# tetris_bigger_mega.net
KiCad netlist of a schematic drawn in EAGLE
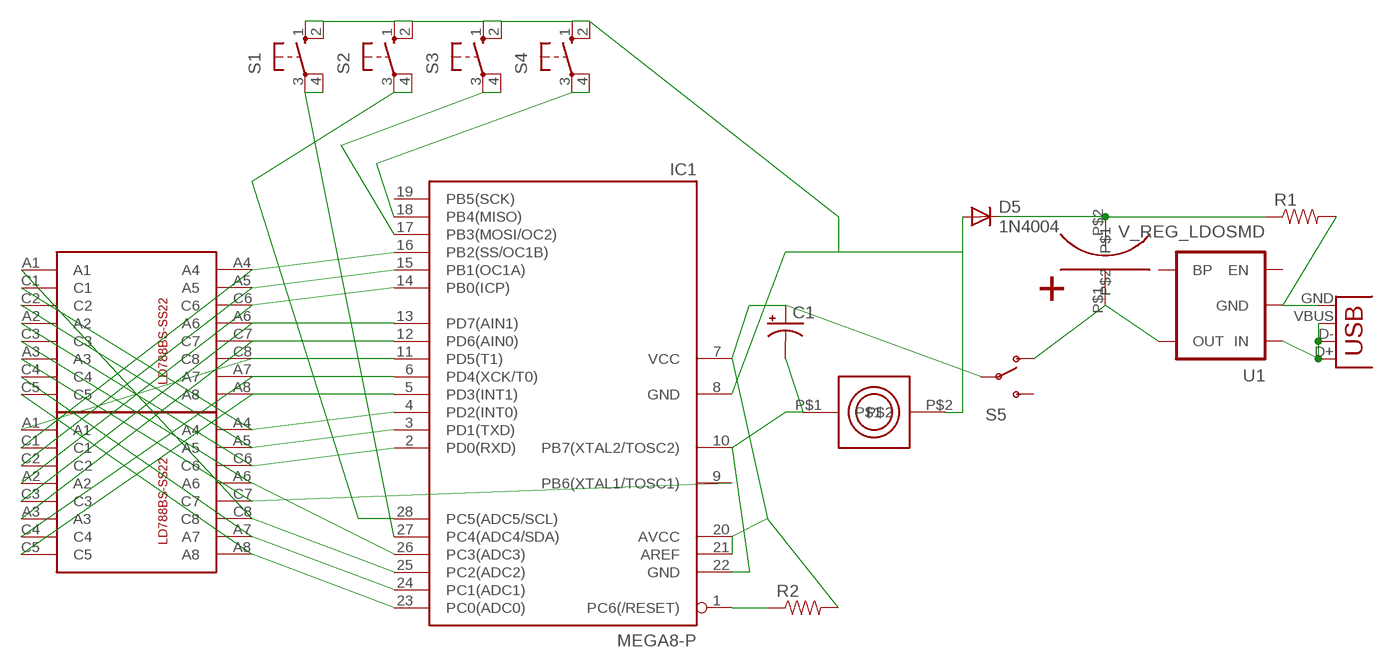
[diagram p0: schematic, sheet 1]

(export (version "E")
  (design (tool "Eeschema 10.0.6"))
  (components
    (comp (ref "C1")
      (value "CAP_POLPTH1")
      (footprint "eagle-import:CPOL-RADIAL-100UF-25V")
      (libsource (lib "eagle-import") (part "CAP_POLPTH1"))
    )
    (comp (ref "D5")
      (value "1N4004")
      (footprint "eagle-import:DO41-10")
      (libsource (lib "eagle-import") (part "1N4004"))
    )
    (comp (ref "IC1")
      (value "MEGA8-P")
      (footprint "eagle-import:DIL28-3")
      (libsource (lib "eagle-import") (part "MEGA8-P"))
    )
    (comp (ref "R1")
      (value "RESISTORPTH1")
      (footprint "eagle-import:AXIAL-0.3")
      (libsource (lib "eagle-import") (part "RESISTORPTH1"))
    )
    (comp (ref "R2")
      (value "RESISTORPTH1")
      (footprint "eagle-import:AXIAL-0.3")
      (libsource (lib "eagle-import") (part "RESISTORPTH1"))
    )
    (comp (ref "S1")
      (value "10-XX")
      (footprint "eagle-import:B3F-10XX")
      (fields (field (name "MPN") "B3F-1000"))
      (libsource (lib "eagle-import") (part "10-XX"))
    )
    (comp (ref "S2")
      (value "10-XX")
      (footprint "eagle-import:B3F-10XX")
      (fields (field (name "MPN") "B3F-1000"))
      (libsource (lib "eagle-import") (part "10-XX"))
    )
    (comp (ref "S3")
      (value "10-XX")
      (footprint "eagle-import:B3F-10XX")
      (fields (field (name "MPN") "B3F-1000"))
      (libsource (lib "eagle-import") (part "10-XX"))
    )
    (comp (ref "S4")
      (value "10-XX")
      (footprint "eagle-import:B3F-10XX")
      (fields (field (name "MPN") "B3F-1000"))
      (libsource (lib "eagle-import") (part "10-XX"))
    )
    (comp (ref "S5")
      (value "SWITCH-SPSTSMD2")
      (footprint "eagle-import:SWITCH-SPDT-SMD")
      (libsource (lib "eagle-import") (part "SWITCH-SPSTSMD2"))
    )
    (comp (ref "U$1")
      (value "LD-1088BS")
      (footprint "eagle-import:LD-1088BS")
      (libsource (lib "eagle-import") (part "LD-1088BS"))
    )
    (comp (ref "U$2")
      (value "LD-1088BS")
      (footprint "eagle-import:LD-1088BS")
      (libsource (lib "eagle-import") (part "LD-1088BS"))
    )
    (comp (ref "U$4")
      (value "I-80450RF")
      (footprint "eagle-import:ISK4.1K_I-80450RF_I2G")
      (libsource (lib "eagle-import") (part "I-80450RF"))
    )
    (comp (ref "U$5")
      (value "NICHICON_12F")
      (footprint "eagle-import:NICHICON_10X30")
      (libsource (lib "eagle-import") (part "NICHICON_12F"))
    )
    (comp (ref "U1")
      (value "V_REG_LDOSMD")
      (footprint "eagle-import:SOT23-5")
      (libsource (lib "eagle-import") (part "V_REG_LDOSMD"))
    )
    (comp (ref "X1")
      (value "USB-MICROB")
      (footprint "eagle-import:USB-MICROB")
      (libsource (lib "eagle-import") (part "USB-MICROB"))
    )
  )
  (nets
    (net (code "1") (name "Net-(C1-+)") (class "Default")
      (node (ref "C1") (pin "1") (pinfunction "+_1") (pintype "passive"))
      (node (ref "IC1") (pin "20") (pinfunction "AVCC_20") (pintype "power_in"))
      (node (ref "IC1") (pin "21") (pinfunction "AREF_21") (pintype "passive"))
      (node (ref "IC1") (pin "7") (pinfunction "VCC_7") (pintype "power_in"))
      (node (ref "R2") (pin "P$2") (pinfunction "2_P$2") (pintype "passive"))
      (node (ref "S5") (pin "2") (pinfunction "P_2") (pintype "passive"))
    )
    (net (code "2") (name "Net-(C1--)") (class "Default")
      (node (ref "C1") (pin "2") (pinfunction "-_2") (pintype "passive"))
      (node (ref "IC1") (pin "10") (pinfunction "PB7(XTAL2/TOSC2)_10") (pintype "bidirectional"))
      (node (ref "IC1") (pin "22") (pinfunction "GND_22") (pintype "power_in"))
      (node (ref "U$4") (pin "P$1") (pinfunction "P$1_P$1") (pintype "bidirectional"))
    )
    (net (code "3") (name "Net-(IC1-PB0(ICP))") (class "Default")
      (node (ref "IC1") (pin "14") (pinfunction "PB0(ICP)_14") (pintype "bidirectional"))
      (node (ref "U$1") (pin "A2") (pinfunction "A2_A2") (pintype "bidirectional"))
      (node (ref "U$2") (pin "C6") (pinfunction "C6_C6") (pintype "bidirectional"))
    )
    (net (code "4") (name "Net-(IC1-PB1(OC1A))") (class "Default")
      (node (ref "IC1") (pin "15") (pinfunction "PB1(OC1A)_15") (pintype "bidirectional"))
      (node (ref "U$1") (pin "C2") (pinfunction "C2_C2") (pintype "bidirectional"))
      (node (ref "U$2") (pin "A5") (pinfunction "A5_A5") (pintype "bidirectional"))
    )
    (net (code "5") (name "Net-(IC1-PB2(SS{slash}OC1B))") (class "Default")
      (node (ref "IC1") (pin "16") (pinfunction "PB2(SS/OC1B)_16") (pintype "bidirectional"))
      (node (ref "U$1") (pin "C1") (pinfunction "C1_C1") (pintype "bidirectional"))
      (node (ref "U$2") (pin "A4") (pinfunction "A4_A4") (pintype "bidirectional"))
    )
    (net (code "6") (name "Net-(IC1-PB3(MOSI{slash}OC2))") (class "Default")
      (node (ref "IC1") (pin "17") (pinfunction "PB3(MOSI/OC2)_17") (pintype "bidirectional"))
      (node (ref "S3") (pin "3") (pinfunction "P_3") (pintype "passive"))
      (node (ref "S3") (pin "4") (pinfunction "P1_4") (pintype "passive"))
    )
    (net (code "7") (name "Net-(IC1-PB4(MISO))") (class "Default")
      (node (ref "IC1") (pin "18") (pinfunction "PB4(MISO)_18") (pintype "bidirectional"))
      (node (ref "S4") (pin "3") (pinfunction "P_3") (pintype "passive"))
      (node (ref "S4") (pin "4") (pinfunction "P1_4") (pintype "passive"))
    )
    (net (code "8") (name "Net-(IC1-PB6(XTAL1{slash}TOSC1))") (class "Default")
      (node (ref "IC1") (pin "9") (pinfunction "PB6(XTAL1/TOSC1)_9") (pintype "bidirectional"))
      (node (ref "U$1") (pin "C7") (pinfunction "C7_C7") (pintype "bidirectional"))
      (node (ref "U$2") (pin "A3") (pinfunction "A3_A3") (pintype "bidirectional"))
    )
    (net (code "9") (name "Net-(IC1-PC0(ADC0))") (class "Default")
      (node (ref "IC1") (pin "23") (pinfunction "PC0(ADC0)_23") (pintype "bidirectional"))
      (node (ref "U$1") (pin "A8") (pinfunction "A8_A8") (pintype "bidirectional"))
      (node (ref "U$2") (pin "C5") (pinfunction "C5_C5") (pintype "bidirectional"))
    )
    (net (code "10") (name "Net-(IC1-PC1(ADC1))") (class "Default")
      (node (ref "IC1") (pin "24") (pinfunction "PC1(ADC1)_24") (pintype "bidirectional"))
      (node (ref "U$1") (pin "A7") (pinfunction "A7_A7") (pintype "bidirectional"))
      (node (ref "U$2") (pin "C4") (pinfunction "C4_C4") (pintype "bidirectional"))
    )
    (net (code "11") (name "Net-(IC1-PC2(ADC2))") (class "Default")
      (node (ref "IC1") (pin "25") (pinfunction "PC2(ADC2)_25") (pintype "bidirectional"))
      (node (ref "U$1") (pin "C8") (pinfunction "C8_C8") (pintype "bidirectional"))
      (node (ref "U$2") (pin "A1") (pinfunction "A1_A1") (pintype "bidirectional"))
    )
    (net (code "12") (name "Net-(IC1-PC3(ADC3))") (class "Default")
      (node (ref "IC1") (pin "26") (pinfunction "PC3(ADC3)_26") (pintype "bidirectional"))
      (node (ref "U$1") (pin "A6") (pinfunction "A6_A6") (pintype "bidirectional"))
      (node (ref "U$2") (pin "C3") (pinfunction "C3_C3") (pintype "bidirectional"))
    )
    (net (code "13") (name "Net-(IC1-PC4(ADC4{slash}SDA))") (class "Default")
      (node (ref "IC1") (pin "27") (pinfunction "PC4(ADC4/SDA)_27") (pintype "bidirectional"))
      (node (ref "S1") (pin "3") (pinfunction "P_3") (pintype "passive"))
      (node (ref "S1") (pin "4") (pinfunction "P1_4") (pintype "passive"))
    )
    (net (code "14") (name "Net-(IC1-PC5(ADC5{slash}SCL))") (class "Default")
      (node (ref "IC1") (pin "28") (pinfunction "PC5(ADC5/SCL)_28") (pintype "bidirectional"))
      (node (ref "S2") (pin "3") (pinfunction "P_3") (pintype "passive"))
      (node (ref "S2") (pin "4") (pinfunction "P1_4") (pintype "passive"))
    )
    (net (code "15") (name "Net-(IC1-PC6({slash}RESET))") (class "Default")
      (node (ref "IC1") (pin "1") (pinfunction "PC6(/RESET)_1") (pintype "bidirectional"))
      (node (ref "R2") (pin "P$1") (pinfunction "1_P$1") (pintype "passive"))
    )
    (net (code "16") (name "Net-(IC1-PD0(RXD))") (class "Default")
      (node (ref "IC1") (pin "2") (pinfunction "PD0(RXD)_2") (pintype "bidirectional"))
      (node (ref "U$1") (pin "C6") (pinfunction "C6_C6") (pintype "bidirectional"))
      (node (ref "U$2") (pin "A2") (pinfunction "A2_A2") (pintype "bidirectional"))
    )
    (net (code "17") (name "Net-(IC1-PD1(TXD))") (class "Default")
      (node (ref "IC1") (pin "3") (pinfunction "PD1(TXD)_3") (pintype "bidirectional"))
      (node (ref "U$1") (pin "A5") (pinfunction "A5_A5") (pintype "bidirectional"))
      (node (ref "U$2") (pin "C2") (pinfunction "C2_C2") (pintype "bidirectional"))
    )
    (net (code "18") (name "Net-(IC1-PD2(INT0))") (class "Default")
      (node (ref "IC1") (pin "4") (pinfunction "PD2(INT0)_4") (pintype "bidirectional"))
      (node (ref "U$1") (pin "A4") (pinfunction "A4_A4") (pintype "bidirectional"))
      (node (ref "U$2") (pin "C1") (pinfunction "C1_C1") (pintype "bidirectional"))
    )
    (net (code "19") (name "Net-(IC1-PD3(INT1))") (class "Default")
      (node (ref "IC1") (pin "5") (pinfunction "PD3(INT1)_5") (pintype "bidirectional"))
      (node (ref "U$1") (pin "C5") (pinfunction "C5_C5") (pintype "bidirectional"))
      (node (ref "U$2") (pin "A8") (pinfunction "A8_A8") (pintype "bidirectional"))
    )
    (net (code "20") (name "Net-(IC1-PD4(XCK{slash}T0))") (class "Default")
      (node (ref "IC1") (pin "6") (pinfunction "PD4(XCK/T0)_6") (pintype "bidirectional"))
      (node (ref "U$1") (pin "C4") (pinfunction "C4_C4") (pintype "bidirectional"))
      (node (ref "U$2") (pin "A7") (pinfunction "A7_A7") (pintype "bidirectional"))
    )
    (net (code "21") (name "Net-(IC1-PD5(T1))") (class "Default")
      (node (ref "IC1") (pin "11") (pinfunction "PD5(T1)_11") (pintype "bidirectional"))
      (node (ref "U$1") (pin "A1") (pinfunction "A1_A1") (pintype "bidirectional"))
      (node (ref "U$2") (pin "C8") (pinfunction "C8_C8") (pintype "bidirectional"))
    )
    (net (code "22") (name "Net-(IC1-PD6(AIN0))") (class "Default")
      (node (ref "IC1") (pin "12") (pinfunction "PD6(AIN0)_12") (pintype "bidirectional"))
      (node (ref "U$1") (pin "A3") (pinfunction "A3_A3") (pintype "bidirectional"))
      (node (ref "U$2") (pin "C7") (pinfunction "C7_C7") (pintype "bidirectional"))
    )
    (net (code "23") (name "Net-(IC1-PD7(AIN1))") (class "Default")
      (node (ref "IC1") (pin "13") (pinfunction "PD7(AIN1)_13") (pintype "bidirectional"))
      (node (ref "U$1") (pin "C3") (pinfunction "C3_C3") (pintype "bidirectional"))
      (node (ref "U$2") (pin "A6") (pinfunction "A6_A6") (pintype "bidirectional"))
    )
    (net (code "24") (name "Net-(R1-1)") (class "Default")
      (node (ref "D5") (pin "C") (pinfunction "C_C") (pintype "passive"))
      (node (ref "R1") (pin "P$1") (pinfunction "1_P$1") (pintype "passive"))
      (node (ref "U$5") (pin "P$2") (pinfunction "P$2_P$2") (pintype "bidirectional"))
    )
    (net (code "25") (name "Net-(R1-2)") (class "Default")
      (node (ref "R1") (pin "P$2") (pinfunction "2_P$2") (pintype "passive"))
      (node (ref "U1") (pin "2") (pinfunction "GND_2") (pintype "input"))
      (node (ref "X1") (pin "GND") (pinfunction "GND_GND") (pintype "bidirectional"))
    )
    (net (code "26") (name "Net-(S1-S)") (class "Default")
      (node (ref "D5") (pin "A") (pinfunction "A_A") (pintype "passive"))
      (node (ref "IC1") (pin "8") (pinfunction "GND_8") (pintype "power_in"))
      (node (ref "S1") (pin "1") (pinfunction "S_1") (pintype "passive"))
      (node (ref "S1") (pin "2") (pinfunction "S1_2") (pintype "passive"))
      (node (ref "S2") (pin "1") (pinfunction "S_1") (pintype "passive"))
      (node (ref "S2") (pin "2") (pinfunction "S1_2") (pintype "passive"))
      (node (ref "S3") (pin "1") (pinfunction "S_1") (pintype "passive"))
      (node (ref "S3") (pin "2") (pinfunction "S1_2") (pintype "passive"))
      (node (ref "S4") (pin "1") (pinfunction "S_1") (pintype "passive"))
      (node (ref "S4") (pin "2") (pinfunction "S1_2") (pintype "passive"))
      (node (ref "U$4") (pin "P$2") (pinfunction "P$2_P$2") (pintype "bidirectional"))
    )
    (net (code "27") (name "Net-(S5-O)") (class "Default")
      (node (ref "S5") (pin "1") (pinfunction "O_1") (pintype "passive"))
      (node (ref "U$5") (pin "P$1") (pinfunction "P$1_P$1") (pintype "bidirectional"))
      (node (ref "U1") (pin "5") (pinfunction "OUT_5") (pintype "passive"))
    )
    (net (code "28") (name "Net-(U1-IN)") (class "Default")
      (node (ref "U1") (pin "1") (pinfunction "IN_1") (pintype "input"))
      (node (ref "X1") (pin "D+") (pinfunction "D+_D+") (pintype "bidirectional"))
      (node (ref "X1") (pin "D-") (pinfunction "D-_D-") (pintype "bidirectional"))
      (node (ref "X1") (pin "VBUS") (pinfunction "VBUS_VBUS") (pintype "bidirectional"))
    )
    (net (code "29") (name "unconnected-(IC1-PB5(SCK)-Pad19)") (class "Default")
      (node (ref "IC1") (pin "19") (pinfunction "PB5(SCK)_19") (pintype "bidirectional"))
    )
    (net (code "30") (name "unconnected-(S5-S-Pad3)") (class "Default")
      (node (ref "S5") (pin "3") (pinfunction "S_3") (pintype "passive"))
    )
    (net (code "31") (name "unconnected-(U1-BP-Pad4)") (class "Default")
      (node (ref "U1") (pin "4") (pinfunction "BP_4") (pintype "input"))
    )
    (net (code "32") (name "unconnected-(U1-EN-Pad3)") (class "Default")
      (node (ref "U1") (pin "3") (pinfunction "EN_3") (pintype "input"))
    )
  )
)
